# SmartRock_4-pin_EC_Breakout-v4.net
KiCad netlist of a schematic drawn in EAGLE
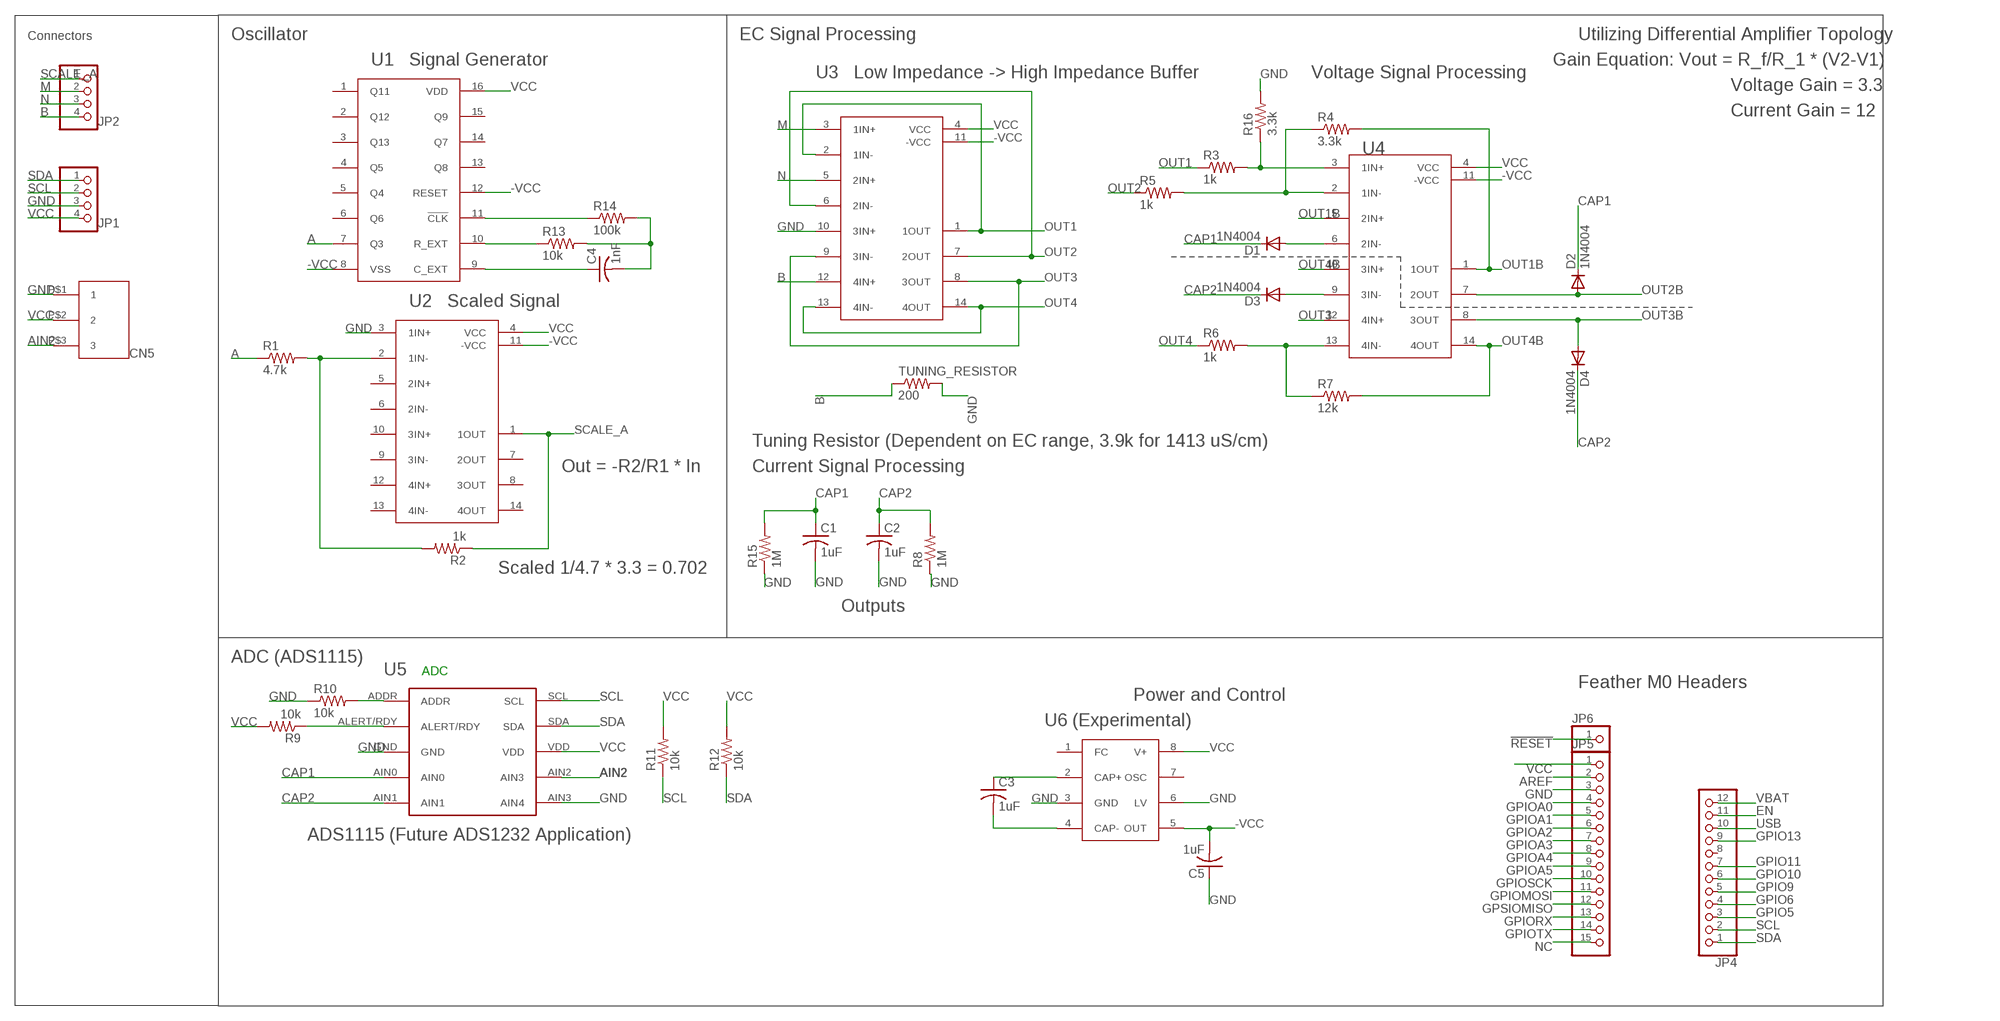
[diagram p0: schematic, sheet 1]

(export (version "E")
  (design (tool "Eeschema 10.0.6"))
  (components
    (comp (ref "C1")
      (value "1uF")
      (footprint "eagle-import:C025-024X044")
      (libsource (lib "eagle-import") (part "C-US025-024X044"))
    )
    (comp (ref "C2")
      (value "1uF")
      (footprint "eagle-import:C025-024X044")
      (libsource (lib "eagle-import") (part "C-US025-024X044"))
    )
    (comp (ref "C3")
      (value "1uF")
      (footprint "eagle-import:C025-024X044")
      (libsource (lib "eagle-import") (part "C-US025-024X044"))
    )
    (comp (ref "C4")
      (value "1nF")
      (footprint "eagle-import:C1206")
      (libsource (lib "eagle-import") (part "C-USC1206"))
    )
    (comp (ref "C5")
      (value "1uF")
      (footprint "eagle-import:C025-024X044")
      (libsource (lib "eagle-import") (part "C-US025-024X044"))
    )
    (comp (ref "CN2")
      (value "JST_3PIN_2MM")
      (footprint "eagle-import:JST_3PIN_2MM")
      (libsource (lib "eagle-import") (part "JST_3PIN_2MM"))
    )
    (comp (ref "D1")
      (value "1N4004")
      (footprint "eagle-import:DO41-10")
      (libsource (lib "eagle-import") (part "1N4004"))
    )
    (comp (ref "D2")
      (value "1N4004")
      (footprint "eagle-import:DO41-10")
      (libsource (lib "eagle-import") (part "1N4004"))
    )
    (comp (ref "D3")
      (value "1N4004")
      (footprint "eagle-import:DO41-10")
      (libsource (lib "eagle-import") (part "1N4004"))
    )
    (comp (ref "D4")
      (value "1N4004")
      (footprint "eagle-import:DO41-10")
      (libsource (lib "eagle-import") (part "1N4004"))
    )
    (comp (ref "JP1")
      (value "PINHD-1X4")
      (footprint "eagle-import:1X04")
      (libsource (lib "eagle-import") (part "PINHD-1X4"))
    )
    (comp (ref "JP2")
      (value "PINHD-1X4")
      (footprint "eagle-import:1X04")
      (libsource (lib "eagle-import") (part "PINHD-1X4"))
    )
    (comp (ref "JP4")
      (value "PINHD-1X12-CB")
      (footprint "eagle-import:1X12-CB")
      (libsource (lib "eagle-import") (part "PINHD-1X12-CB"))
    )
    (comp (ref "JP5")
      (value "PINHD-1X15-CB")
      (footprint "eagle-import:1X15-CB")
      (libsource (lib "eagle-import") (part "PINHD-1X15-CB"))
    )
    (comp (ref "JP6")
      (value "PINHD-1X1CB")
      (footprint "eagle-import:1X01-CLEANBIG")
      (libsource (lib "eagle-import") (part "PINHD-1X1CB"))
    )
    (comp (ref "R1")
      (value "4.7k")
      (footprint "eagle-import:M1206")
      (libsource (lib "eagle-import") (part "R-US_M1206"))
    )
    (comp (ref "R2")
      (value "1k")
      (footprint "eagle-import:M1206")
      (libsource (lib "eagle-import") (part "R-US_M1206"))
    )
    (comp (ref "R3")
      (value "1k")
      (footprint "eagle-import:M1206")
      (libsource (lib "eagle-import") (part "R-US_M1206"))
    )
    (comp (ref "R4")
      (value "3.3k")
      (footprint "eagle-import:M1206")
      (libsource (lib "eagle-import") (part "R-US_M1206"))
    )
    (comp (ref "R5")
      (value "1k")
      (footprint "eagle-import:M1206")
      (libsource (lib "eagle-import") (part "R-US_M1206"))
    )
    (comp (ref "R6")
      (value "1k")
      (footprint "eagle-import:M1206")
      (libsource (lib "eagle-import") (part "R-US_M1206"))
    )
    (comp (ref "R7")
      (value "12k")
      (footprint "eagle-import:M1206")
      (libsource (lib "eagle-import") (part "R-US_M1206"))
    )
    (comp (ref "R8")
      (value "1M")
      (footprint "eagle-import:M1206")
      (libsource (lib "eagle-import") (part "R-US_M1206"))
    )
    (comp (ref "R9")
      (value "10k")
      (footprint "eagle-import:M1206")
      (libsource (lib "eagle-import") (part "R-US_M1206"))
    )
    (comp (ref "R10")
      (value "10k")
      (footprint "eagle-import:M1206")
      (libsource (lib "eagle-import") (part "R-US_M1206"))
    )
    (comp (ref "R11")
      (value "10k")
      (footprint "eagle-import:M1206")
      (libsource (lib "eagle-import") (part "R-US_M1206"))
    )
    (comp (ref "R12")
      (value "10k")
      (footprint "eagle-import:M1206")
      (libsource (lib "eagle-import") (part "R-US_M1206"))
    )
    (comp (ref "R13")
      (value "10k")
      (footprint "eagle-import:M1206")
      (libsource (lib "eagle-import") (part "R-US_M1206"))
    )
    (comp (ref "R14")
      (value "100k")
      (footprint "eagle-import:M1206")
      (libsource (lib "eagle-import") (part "R-US_M1206"))
    )
    (comp (ref "R15")
      (value "1M")
      (footprint "eagle-import:M1206")
      (libsource (lib "eagle-import") (part "R-US_M1206"))
    )
    (comp (ref "R16")
      (value "3.3k")
      (footprint "eagle-import:M1206")
      (libsource (lib "eagle-import") (part "R-US_M1206"))
    )
    (comp (ref "TUNING_RESISTOR")
      (value "200")
      (footprint "eagle-import:M1206")
      (libsource (lib "eagle-import") (part "R-US_M1206"))
    )
    (comp (ref "U1")
      (value "CD4060BPWR")
      (footprint "eagle-import:CD4060BPWR")
      (libsource (lib "eagle-import") (part "CD4060BPWR"))
    )
    (comp (ref "U2")
      (value "TL074CPWR")
      (footprint "eagle-import:LT074CPWR")
      (libsource (lib "eagle-import") (part "TL074CPWR"))
    )
    (comp (ref "U3")
      (value "TL074CPWR")
      (footprint "eagle-import:LT074CPWR")
      (libsource (lib "eagle-import") (part "TL074CPWR"))
    )
    (comp (ref "U4")
      (value "TL074CPWR")
      (footprint "eagle-import:LT074CPWR")
      (libsource (lib "eagle-import") (part "TL074CPWR"))
    )
    (comp (ref "U5")
      (value "ADS1115")
      (footprint "eagle-import:ADS1115")
      (libsource (lib "eagle-import") (part "ADS1115"))
    )
    (comp (ref "U6+")
      (value "MAX660MX/NOPB")
      (footprint "eagle-import:MAX660MX_NOPB")
      (libsource (lib "eagle-import") (part "MAX660MX/NOPB"))
    )
  )
  (nets
    (net (code "1") (name "/-VCC") (class "Default")
      (node (ref "C5") (pin "2") (pinfunction "2_2") (pintype "passive"))
      (node (ref "U1") (pin "12") (pinfunction "RESET_12") (pintype "bidirectional"))
      (node (ref "U1") (pin "8") (pinfunction "VSS_8") (pintype "bidirectional"))
      (node (ref "U2") (pin "11") (pinfunction "-VCC_11") (pintype "bidirectional"))
      (node (ref "U3") (pin "11") (pinfunction "-VCC_11") (pintype "bidirectional"))
      (node (ref "U4") (pin "11") (pinfunction "-VCC_11") (pintype "bidirectional"))
      (node (ref "U6+") (pin "5") (pinfunction "OUT_5") (pintype "bidirectional"))
    )
    (net (code "2") (name "/A") (class "Default")
      (node (ref "R1") (pin "1") (pinfunction "1_1") (pintype "passive"))
      (node (ref "U1") (pin "7") (pinfunction "Q3_7") (pintype "bidirectional"))
    )
    (net (code "3") (name "/AIN2") (class "Default")
      (node (ref "CN2") (pin "P$3") (pinfunction "3_P$3") (pintype "bidirectional"))
      (node (ref "U5") (pin "AIN2") (pinfunction "AIN3_AIN2") (pintype "bidirectional"))
    )
    (net (code "4") (name "/AREF") (class "Default")
      (node (ref "JP5") (pin "2") (pinfunction "2_2") (pintype "passive"))
    )
    (net (code "5") (name "/B") (class "Default")
      (node (ref "JP2") (pin "4") (pinfunction "4_4") (pintype "passive"))
      (node (ref "TUNING_RESISTOR") (pin "1") (pinfunction "1_1") (pintype "passive"))
      (node (ref "U3") (pin "12") (pinfunction "4IN+_12") (pintype "bidirectional"))
    )
    (net (code "6") (name "/CAP1") (class "Default")
      (node (ref "C1") (pin "1") (pinfunction "1_1") (pintype "passive"))
      (node (ref "D1") (pin "C") (pinfunction "C_C") (pintype "passive"))
      (node (ref "D2") (pin "C") (pinfunction "C_C") (pintype "passive"))
      (node (ref "R15") (pin "2") (pinfunction "2_2") (pintype "passive"))
      (node (ref "U5") (pin "AIN0") (pinfunction "AIN0_AIN0") (pintype "bidirectional"))
    )
    (net (code "7") (name "/CAP2") (class "Default")
      (node (ref "C2") (pin "1") (pinfunction "1_1") (pintype "passive"))
      (node (ref "D3") (pin "C") (pinfunction "C_C") (pintype "passive"))
      (node (ref "D4") (pin "C") (pinfunction "C_C") (pintype "passive"))
      (node (ref "R8") (pin "2") (pinfunction "2_2") (pintype "passive"))
      (node (ref "U5") (pin "AIN1") (pinfunction "AIN1_AIN1") (pintype "bidirectional"))
    )
    (net (code "8") (name "/EN") (class "Default")
      (node (ref "JP4") (pin "11") (pinfunction "11_11") (pintype "passive"))
    )
    (net (code "9") (name "/GND") (class "Default")
      (node (ref "C1") (pin "2") (pinfunction "2_2") (pintype "passive"))
      (node (ref "C2") (pin "2") (pinfunction "2_2") (pintype "passive"))
      (node (ref "C5") (pin "1") (pinfunction "1_1") (pintype "passive"))
      (node (ref "CN2") (pin "P$1") (pinfunction "1_P$1") (pintype "bidirectional"))
      (node (ref "JP1") (pin "3") (pinfunction "3_3") (pintype "passive"))
      (node (ref "JP5") (pin "3") (pinfunction "3_3") (pintype "passive"))
      (node (ref "R10") (pin "1") (pinfunction "1_1") (pintype "passive"))
      (node (ref "R15") (pin "1") (pinfunction "1_1") (pintype "passive"))
      (node (ref "R16") (pin "2") (pinfunction "2_2") (pintype "passive"))
      (node (ref "R8") (pin "1") (pinfunction "1_1") (pintype "passive"))
      (node (ref "TUNING_RESISTOR") (pin "2") (pinfunction "2_2") (pintype "passive"))
      (node (ref "U2") (pin "3") (pinfunction "1IN+_3") (pintype "bidirectional"))
      (node (ref "U3") (pin "10") (pinfunction "3IN+_10") (pintype "bidirectional"))
      (node (ref "U5") (pin "AIN3") (pinfunction "AIN4_AIN3") (pintype "bidirectional"))
      (node (ref "U5") (pin "GND") (pinfunction "GND_GND") (pintype "bidirectional"))
      (node (ref "U6+") (pin "3") (pinfunction "GND_3") (pintype "bidirectional"))
      (node (ref "U6+") (pin "6") (pinfunction "LV_6") (pintype "bidirectional"))
    )
    (net (code "10") (name "/GPIO5") (class "Default")
      (node (ref "JP4") (pin "3") (pinfunction "3_3") (pintype "passive"))
    )
    (net (code "11") (name "/GPIO6") (class "Default")
      (node (ref "JP4") (pin "4") (pinfunction "4_4") (pintype "passive"))
    )
    (net (code "12") (name "/GPIO9") (class "Default")
      (node (ref "JP4") (pin "5") (pinfunction "5_5") (pintype "passive"))
    )
    (net (code "13") (name "/GPIO10") (class "Default")
      (node (ref "JP4") (pin "6") (pinfunction "6_6") (pintype "passive"))
    )
    (net (code "14") (name "/GPIO11") (class "Default")
      (node (ref "JP4") (pin "7") (pinfunction "7_7") (pintype "passive"))
    )
    (net (code "15") (name "/GPIO13") (class "Default")
      (node (ref "JP4") (pin "9") (pinfunction "9_9") (pintype "passive"))
    )
    (net (code "16") (name "/GPIOA0") (class "Default")
      (node (ref "JP5") (pin "4") (pinfunction "4_4") (pintype "passive"))
    )
    (net (code "17") (name "/GPIOA1") (class "Default")
      (node (ref "JP5") (pin "5") (pinfunction "5_5") (pintype "passive"))
    )
    (net (code "18") (name "/GPIOA2") (class "Default")
      (node (ref "JP5") (pin "6") (pinfunction "6_6") (pintype "passive"))
    )
    (net (code "19") (name "/GPIOA3") (class "Default")
      (node (ref "JP5") (pin "7") (pinfunction "7_7") (pintype "passive"))
    )
    (net (code "20") (name "/GPIOA4") (class "Default")
      (node (ref "JP5") (pin "8") (pinfunction "8_8") (pintype "passive"))
    )
    (net (code "21") (name "/GPIOA5") (class "Default")
      (node (ref "JP5") (pin "9") (pinfunction "9_9") (pintype "passive"))
    )
    (net (code "22") (name "/GPIOMOSI") (class "Default")
      (node (ref "JP5") (pin "11") (pinfunction "11_11") (pintype "passive"))
    )
    (net (code "23") (name "/GPIORX") (class "Default")
      (node (ref "JP5") (pin "13") (pinfunction "13_13") (pintype "passive"))
    )
    (net (code "24") (name "/GPIOSCK") (class "Default")
      (node (ref "JP5") (pin "10") (pinfunction "10_10") (pintype "passive"))
    )
    (net (code "25") (name "/GPIOTX") (class "Default")
      (node (ref "JP5") (pin "14") (pinfunction "14_14") (pintype "passive"))
    )
    (net (code "26") (name "/GPSIOMISO") (class "Default")
      (node (ref "JP5") (pin "12") (pinfunction "12_12") (pintype "passive"))
    )
    (net (code "27") (name "/M") (class "Default")
      (node (ref "JP2") (pin "2") (pinfunction "2_2") (pintype "passive"))
      (node (ref "U3") (pin "3") (pinfunction "1IN+_3") (pintype "bidirectional"))
    )
    (net (code "28") (name "/N") (class "Default")
      (node (ref "JP2") (pin "3") (pinfunction "3_3") (pintype "passive"))
      (node (ref "U3") (pin "5") (pinfunction "2IN+_5") (pintype "bidirectional"))
    )
    (net (code "29") (name "/NC") (class "Default")
      (node (ref "JP5") (pin "15") (pinfunction "15_15") (pintype "passive"))
    )
    (net (code "30") (name "/OUT1") (class "Default")
      (node (ref "R3") (pin "1") (pinfunction "1_1") (pintype "passive"))
      (node (ref "U3") (pin "1") (pinfunction "1OUT_1") (pintype "bidirectional"))
      (node (ref "U3") (pin "2") (pinfunction "1IN-_2") (pintype "bidirectional"))
    )
    (net (code "31") (name "/OUT1B") (class "Default")
      (node (ref "R4") (pin "2") (pinfunction "2_2") (pintype "passive"))
      (node (ref "U4") (pin "1") (pinfunction "1OUT_1") (pintype "bidirectional"))
      (node (ref "U4") (pin "5") (pinfunction "2IN+_5") (pintype "bidirectional"))
    )
    (net (code "32") (name "/OUT2") (class "Default")
      (node (ref "R5") (pin "1") (pinfunction "1_1") (pintype "passive"))
      (node (ref "U3") (pin "6") (pinfunction "2IN-_6") (pintype "bidirectional"))
      (node (ref "U3") (pin "7") (pinfunction "2OUT_7") (pintype "bidirectional"))
    )
    (net (code "33") (name "/OUT2B") (class "Default")
      (node (ref "D2") (pin "A") (pinfunction "A_A") (pintype "passive"))
      (node (ref "U4") (pin "7") (pinfunction "2OUT_7") (pintype "bidirectional"))
    )
    (net (code "34") (name "/OUT3") (class "Default")
      (node (ref "U3") (pin "8") (pinfunction "3OUT_8") (pintype "bidirectional"))
      (node (ref "U3") (pin "9") (pinfunction "3IN-_9") (pintype "bidirectional"))
      (node (ref "U4") (pin "12") (pinfunction "4IN+_12") (pintype "bidirectional"))
    )
    (net (code "35") (name "/OUT3B") (class "Default")
      (node (ref "D4") (pin "A") (pinfunction "A_A") (pintype "passive"))
      (node (ref "U4") (pin "8") (pinfunction "3OUT_8") (pintype "bidirectional"))
    )
    (net (code "36") (name "/OUT4") (class "Default")
      (node (ref "R6") (pin "1") (pinfunction "1_1") (pintype "passive"))
      (node (ref "U3") (pin "13") (pinfunction "4IN-_13") (pintype "bidirectional"))
      (node (ref "U3") (pin "14") (pinfunction "4OUT_14") (pintype "bidirectional"))
    )
    (net (code "37") (name "/OUT4B") (class "Default")
      (node (ref "R7") (pin "2") (pinfunction "2_2") (pintype "passive"))
      (node (ref "U4") (pin "10") (pinfunction "3IN+_10") (pintype "bidirectional"))
      (node (ref "U4") (pin "14") (pinfunction "4OUT_14") (pintype "bidirectional"))
    )
    (net (code "38") (name "/SCALE_A") (class "Default")
      (node (ref "JP2") (pin "1") (pinfunction "1_1") (pintype "passive"))
      (node (ref "R2") (pin "1") (pinfunction "1_1") (pintype "passive"))
      (node (ref "U2") (pin "1") (pinfunction "1OUT_1") (pintype "bidirectional"))
    )
    (net (code "39") (name "/SCL") (class "Default")
      (node (ref "JP1") (pin "2") (pinfunction "2_2") (pintype "passive"))
      (node (ref "JP4") (pin "2") (pinfunction "2_2") (pintype "passive"))
      (node (ref "R11") (pin "1") (pinfunction "1_1") (pintype "passive"))
      (node (ref "U5") (pin "SCL") (pinfunction "SCL_SCL") (pintype "bidirectional"))
    )
    (net (code "40") (name "/SDA") (class "Default")
      (node (ref "JP1") (pin "1") (pinfunction "1_1") (pintype "passive"))
      (node (ref "JP4") (pin "1") (pinfunction "1_1") (pintype "passive"))
      (node (ref "R12") (pin "1") (pinfunction "1_1") (pintype "passive"))
      (node (ref "U5") (pin "SDA") (pinfunction "SDA_SDA") (pintype "bidirectional"))
    )
    (net (code "41") (name "/USB") (class "Default")
      (node (ref "JP4") (pin "10") (pinfunction "10_10") (pintype "passive"))
    )
    (net (code "42") (name "/VBAT") (class "Default")
      (node (ref "JP4") (pin "12") (pinfunction "12_12") (pintype "passive"))
    )
    (net (code "43") (name "/VCC") (class "Default")
      (node (ref "CN2") (pin "P$2") (pinfunction "2_P$2") (pintype "bidirectional"))
      (node (ref "JP1") (pin "4") (pinfunction "4_4") (pintype "passive"))
      (node (ref "JP5") (pin "1") (pinfunction "1_1") (pintype "passive"))
      (node (ref "R11") (pin "2") (pinfunction "2_2") (pintype "passive"))
      (node (ref "R12") (pin "2") (pinfunction "2_2") (pintype "passive"))
      (node (ref "R9") (pin "2") (pinfunction "2_2") (pintype "passive"))
      (node (ref "U1") (pin "16") (pinfunction "VDD_16") (pintype "bidirectional"))
      (node (ref "U2") (pin "4") (pinfunction "VCC_4") (pintype "bidirectional"))
      (node (ref "U3") (pin "4") (pinfunction "VCC_4") (pintype "bidirectional"))
      (node (ref "U4") (pin "4") (pinfunction "VCC_4") (pintype "bidirectional"))
      (node (ref "U5") (pin "VDD") (pinfunction "VDD_VDD") (pintype "bidirectional"))
      (node (ref "U6+") (pin "8") (pinfunction "V+_8") (pintype "bidirectional"))
    )
    (net (code "44") (name "/~{RESET}") (class "Default")
      (node (ref "JP6") (pin "1") (pinfunction "1_1") (pintype "passive"))
    )
    (net (code "45") (name "Net-(C4-Pad2)") (class "Default")
      (node (ref "C4") (pin "2") (pinfunction "2_2") (pintype "passive"))
      (node (ref "R13") (pin "2") (pinfunction "2_2") (pintype "passive"))
      (node (ref "R14") (pin "2") (pinfunction "2_2") (pintype "passive"))
    )
    (net (code "46") (name "Net-(R9-Pad1)") (class "Default")
      (node (ref "R9") (pin "1") (pinfunction "1_1") (pintype "passive"))
      (node (ref "U5") (pin "ALERT/RDY") (pinfunction "ALERT/RDY_ALERT/RDY") (pintype "bidirectional"))
    )
    (net (code "47") (name "Net-(R10-Pad2)") (class "Default")
      (node (ref "R10") (pin "2") (pinfunction "2_2") (pintype "passive"))
      (node (ref "U5") (pin "ADDR") (pinfunction "ADDR_ADDR") (pintype "bidirectional"))
    )
    (net (code "48") (name "Net-(U1-C_EXT)") (class "Default")
      (node (ref "C4") (pin "1") (pinfunction "1_1") (pintype "passive"))
      (node (ref "U1") (pin "9") (pinfunction "C_EXT_9") (pintype "bidirectional"))
    )
    (net (code "49") (name "Net-(U1-R_EXT)") (class "Default")
      (node (ref "R13") (pin "1") (pinfunction "1_1") (pintype "passive"))
      (node (ref "U1") (pin "10") (pinfunction "R_EXT_10") (pintype "bidirectional"))
    )
    (net (code "50") (name "Net-(U1-~{CLK})") (class "Default")
      (node (ref "R14") (pin "1") (pinfunction "1_1") (pintype "passive"))
      (node (ref "U1") (pin "11") (pinfunction "~{CLK}_11") (pintype "bidirectional"))
    )
    (net (code "51") (name "Net-(U2-1IN-)") (class "Default")
      (node (ref "R1") (pin "2") (pinfunction "2_2") (pintype "passive"))
      (node (ref "R2") (pin "2") (pinfunction "2_2") (pintype "passive"))
      (node (ref "U2") (pin "2") (pinfunction "1IN-_2") (pintype "bidirectional"))
    )
    (net (code "52") (name "Net-(U4-1IN+)") (class "Default")
      (node (ref "R16") (pin "1") (pinfunction "1_1") (pintype "passive"))
      (node (ref "R3") (pin "2") (pinfunction "2_2") (pintype "passive"))
      (node (ref "U4") (pin "3") (pinfunction "1IN+_3") (pintype "bidirectional"))
    )
    (net (code "53") (name "Net-(U4-1IN-)") (class "Default")
      (node (ref "R4") (pin "1") (pinfunction "1_1") (pintype "passive"))
      (node (ref "R5") (pin "2") (pinfunction "2_2") (pintype "passive"))
      (node (ref "U4") (pin "2") (pinfunction "1IN-_2") (pintype "bidirectional"))
    )
    (net (code "54") (name "Net-(U4-2IN-)") (class "Default")
      (node (ref "D1") (pin "A") (pinfunction "A_A") (pintype "passive"))
      (node (ref "U4") (pin "6") (pinfunction "2IN-_6") (pintype "bidirectional"))
    )
    (net (code "55") (name "Net-(U4-3IN-)") (class "Default")
      (node (ref "D3") (pin "A") (pinfunction "A_A") (pintype "passive"))
      (node (ref "U4") (pin "9") (pinfunction "3IN-_9") (pintype "bidirectional"))
    )
    (net (code "56") (name "Net-(U4-4IN-)") (class "Default")
      (node (ref "R6") (pin "2") (pinfunction "2_2") (pintype "passive"))
      (node (ref "R7") (pin "1") (pinfunction "1_1") (pintype "passive"))
      (node (ref "U4") (pin "13") (pinfunction "4IN-_13") (pintype "bidirectional"))
    )
    (net (code "57") (name "Net-(U6+-CAP+)") (class "Default")
      (node (ref "C3") (pin "1") (pinfunction "1_1") (pintype "passive"))
      (node (ref "U6+") (pin "2") (pinfunction "CAP+_2") (pintype "bidirectional"))
    )
    (net (code "58") (name "Net-(U6+-CAP-)") (class "Default")
      (node (ref "C3") (pin "2") (pinfunction "2_2") (pintype "passive"))
      (node (ref "U6+") (pin "4") (pinfunction "CAP-_4") (pintype "bidirectional"))
    )
    (net (code "59") (name "unconnected-(JP4-Pad8)") (class "Default")
      (node (ref "JP4") (pin "8") (pinfunction "8_8") (pintype "passive"))
    )
    (net (code "60") (name "unconnected-(U1-Q4-Pad5)") (class "Default")
      (node (ref "U1") (pin "5") (pinfunction "Q4_5") (pintype "bidirectional"))
    )
    (net (code "61") (name "unconnected-(U1-Q5-Pad4)") (class "Default")
      (node (ref "U1") (pin "4") (pinfunction "Q5_4") (pintype "bidirectional"))
    )
    (net (code "62") (name "unconnected-(U1-Q6-Pad6)") (class "Default")
      (node (ref "U1") (pin "6") (pinfunction "Q6_6") (pintype "bidirectional"))
    )
    (net (code "63") (name "unconnected-(U1-Q7-Pad14)") (class "Default")
      (node (ref "U1") (pin "14") (pinfunction "Q7_14") (pintype "bidirectional"))
    )
    (net (code "64") (name "unconnected-(U1-Q8-Pad13)") (class "Default")
      (node (ref "U1") (pin "13") (pinfunction "Q8_13") (pintype "bidirectional"))
    )
    (net (code "65") (name "unconnected-(U1-Q9-Pad15)") (class "Default")
      (node (ref "U1") (pin "15") (pinfunction "Q9_15") (pintype "bidirectional"))
    )
    (net (code "66") (name "unconnected-(U1-Q11-Pad1)") (class "Default")
      (node (ref "U1") (pin "1") (pinfunction "Q11_1") (pintype "bidirectional"))
    )
    (net (code "67") (name "unconnected-(U1-Q12-Pad2)") (class "Default")
      (node (ref "U1") (pin "2") (pinfunction "Q12_2") (pintype "bidirectional"))
    )
    (net (code "68") (name "unconnected-(U1-Q13-Pad3)") (class "Default")
      (node (ref "U1") (pin "3") (pinfunction "Q13_3") (pintype "bidirectional"))
    )
    (net (code "69") (name "unconnected-(U2-2IN+-Pad5)") (class "Default")
      (node (ref "U2") (pin "5") (pinfunction "2IN+_5") (pintype "bidirectional"))
    )
    (net (code "70") (name "unconnected-(U2-2IN--Pad6)") (class "Default")
      (node (ref "U2") (pin "6") (pinfunction "2IN-_6") (pintype "bidirectional"))
    )
    (net (code "71") (name "unconnected-(U2-2OUT-Pad7)") (class "Default")
      (node (ref "U2") (pin "7") (pinfunction "2OUT_7") (pintype "bidirectional"))
    )
    (net (code "72") (name "unconnected-(U2-3IN+-Pad10)") (class "Default")
      (node (ref "U2") (pin "10") (pinfunction "3IN+_10") (pintype "bidirectional"))
    )
    (net (code "73") (name "unconnected-(U2-3IN--Pad9)") (class "Default")
      (node (ref "U2") (pin "9") (pinfunction "3IN-_9") (pintype "bidirectional"))
    )
    (net (code "74") (name "unconnected-(U2-3OUT-Pad8)") (class "Default")
      (node (ref "U2") (pin "8") (pinfunction "3OUT_8") (pintype "bidirectional"))
    )
    (net (code "75") (name "unconnected-(U2-4IN+-Pad12)") (class "Default")
      (node (ref "U2") (pin "12") (pinfunction "4IN+_12") (pintype "bidirectional"))
    )
    (net (code "76") (name "unconnected-(U2-4IN--Pad13)") (class "Default")
      (node (ref "U2") (pin "13") (pinfunction "4IN-_13") (pintype "bidirectional"))
    )
    (net (code "77") (name "unconnected-(U2-4OUT-Pad14)") (class "Default")
      (node (ref "U2") (pin "14") (pinfunction "4OUT_14") (pintype "bidirectional"))
    )
    (net (code "78") (name "unconnected-(U6+-FC-Pad1)") (class "Default")
      (node (ref "U6+") (pin "1") (pinfunction "FC_1") (pintype "bidirectional"))
    )
    (net (code "79") (name "unconnected-(U6+-OSC-Pad7)") (class "Default")
      (node (ref "U6+") (pin "7") (pinfunction "OSC_7") (pintype "bidirectional"))
    )
  )
)
